# MicroMultimeter_USB_Sch.net
KiCad netlist of a schematic drawn in Altium Designer
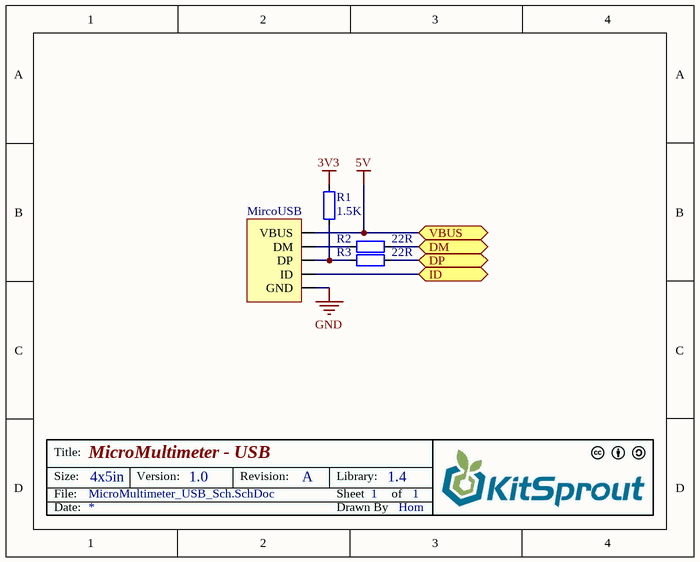
[diagram p0: MicroMultimeter_USB_Sch.SchDoc]

(export (version "E")
  (design (tool "Eeschema 10.0.6"))
  (components
    (comp (ref "MircoUSB")
      (value "USB_Micro")
      (footprint "PCB_USB:USB_Micro-AB")
      (description "USB")
      (libsource (lib "SCH_USB") (part "USB_Micro"))
    )
    (comp (ref "R1")
      (value "1.5K")
      (footprint "PCB_PassiveRes:RES_0603")
      (description "Resistor")
      (fields (field (name "Comment") "Res_0603"))
      (libsource (lib "SCH_Passive") (part "Res_0603"))
    )
    (comp (ref "R2")
      (value "22R")
      (footprint "PCB_PassiveRes:RES_0603")
      (description "Resistor")
      (fields (field (name "Comment") "Res_0603"))
      (libsource (lib "") (part "Res_0603_1"))
    )
    (comp (ref "R3")
      (value "22R")
      (footprint "PCB_PassiveRes:RES_0603")
      (description "Resistor")
      (fields (field (name "Comment") "Res_0603"))
      (libsource (lib "") (part "Res_0603_1"))
    )
  )
  (nets
    (net (code "1") (name "/DM") (class "Default")
      (node (ref "R2") (pin "2") (pinfunction "2_2") (pintype "passive"))
    )
    (net (code "2") (name "/DP") (class "Default")
      (node (ref "R3") (pin "2") (pinfunction "2_2") (pintype "passive"))
    )
    (net (code "3") (name "/ID") (class "Default")
      (node (ref "MircoUSB") (pin "4") (pinfunction "ID_4") (pintype "passive"))
    )
    (net (code "4") (name "3V3") (class "Default")
      (node (ref "R1") (pin "1") (pinfunction "1_1") (pintype "passive"))
    )
    (net (code "5") (name "5V") (class "Default")
      (node (ref "MircoUSB") (pin "1") (pinfunction "VBUS_1") (pintype "passive"))
    )
    (net (code "6") (name "GND") (class "Default")
      (node (ref "MircoUSB") (pin "5") (pinfunction "GND_5") (pintype "passive"))
    )
    (net (code "7") (name "Net-(MircoUSB-DM)") (class "Default")
      (node (ref "MircoUSB") (pin "2") (pinfunction "DM_2") (pintype "passive"))
      (node (ref "R2") (pin "1") (pinfunction "1_1") (pintype "passive"))
    )
    (net (code "8") (name "Net-(MircoUSB-DP)") (class "Default")
      (node (ref "MircoUSB") (pin "3") (pinfunction "DP_3") (pintype "passive"))
      (node (ref "R1") (pin "2") (pinfunction "2_2") (pintype "passive"))
      (node (ref "R3") (pin "1") (pinfunction "1_1") (pintype "passive"))
    )
  )
)
